# GD32F450_External_Expansion_Camera__V1_0.net
KiCad netlist of a schematic drawn in Altium Designer
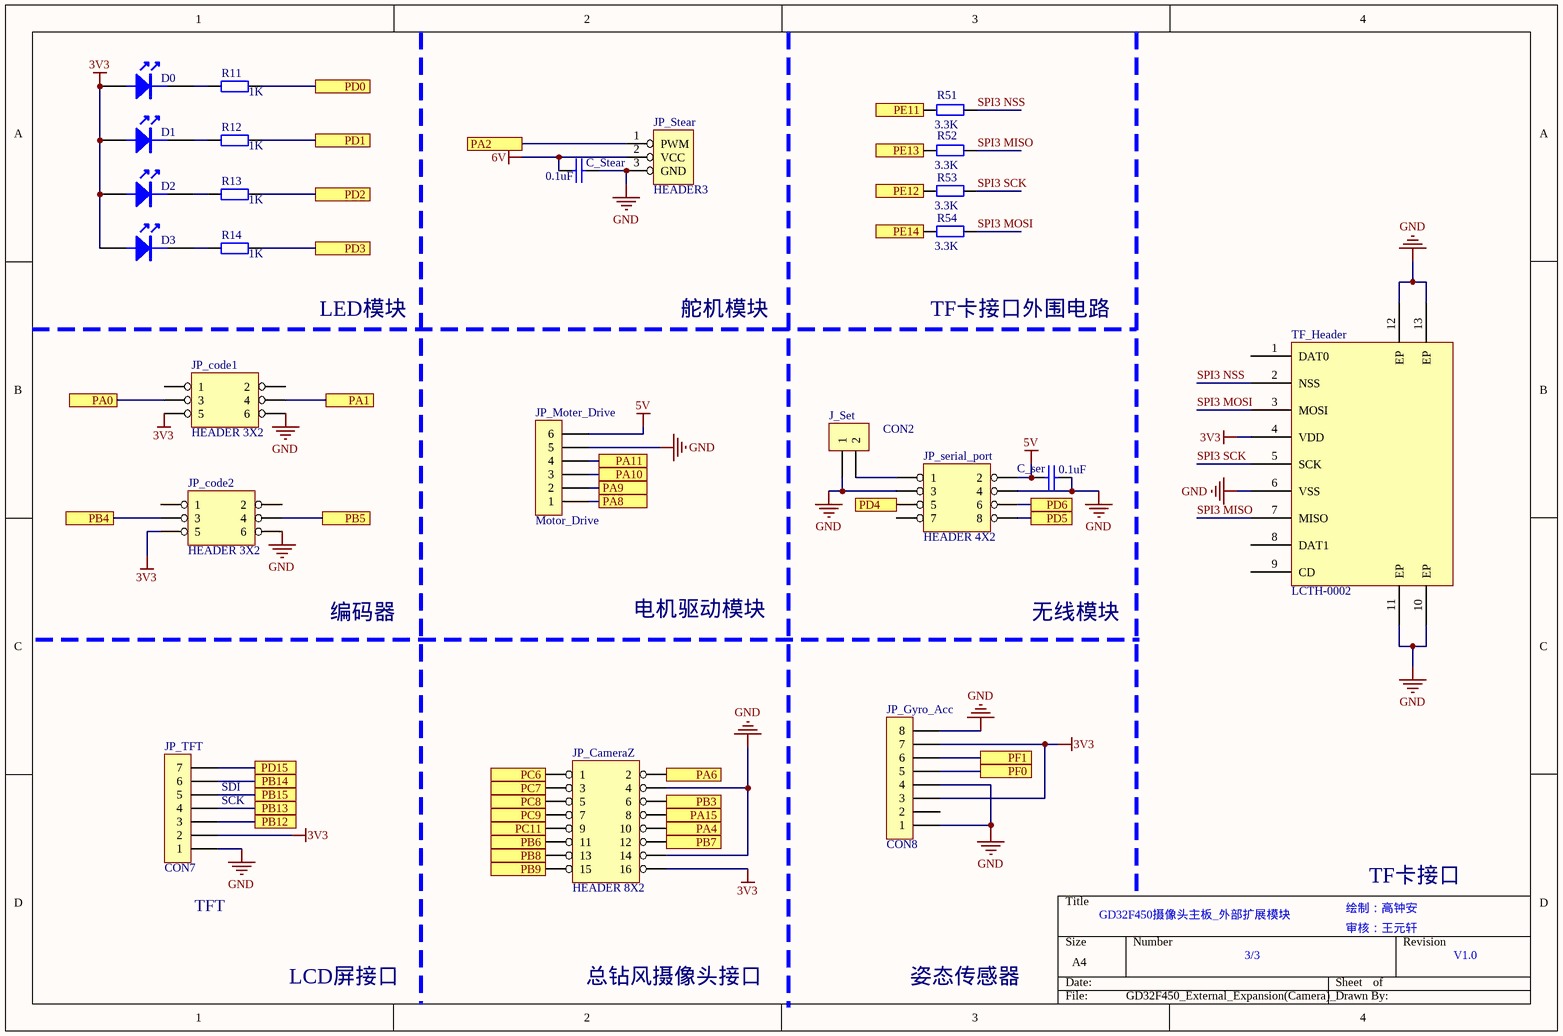
[diagram p0: GD32F450_External_Expansion(Camera)_V1.0.SchDoc]

(export (version "E")
  (design (tool "Eeschema 10.0.6"))
  (components
    (comp (ref "C_ser")
      (value "0.1uF")
      (footprint "0805C")
      (description "Capacitor")
      (libsource (lib "Protel99Lib_SCH") (part "CAP"))
    )
    (comp (ref "C_Stear")
      (value "0.1uF")
      (footprint "0805C")
      (description "Capacitor")
      (libsource (lib "Protel99Lib_SCH") (part "CAP"))
    )
    (comp (ref "D0") (value "LED") (footprint "1206LED") (libsource (lib "Protel99Lib_SCH") (part "LED")))
    (comp (ref "D1") (value "LED") (footprint "1206LED") (libsource (lib "Protel99Lib_SCH") (part "LED")))
    (comp (ref "D2") (value "LED") (footprint "1206LED") (libsource (lib "Protel99Lib_SCH") (part "LED")))
    (comp (ref "D3") (value "LED") (footprint "1206LED") (libsource (lib "Protel99Lib_SCH") (part "LED")))
    (comp (ref "JP_CameraZ")
      (value "HEADER 8X2")
      (footprint "IDC16-JLC")
      (libsource (lib "Protel99Lib_SCH") (part "HEADER 8X2"))
    )
    (comp (ref "JP_code1")
      (value "HEADER 3X2")
      (footprint "IDC6-JLC")
      (libsource (lib "Protel99Lib_SCH") (part "HEADER 3X2"))
    )
    (comp (ref "JP_code2")
      (value "HEADER 3X2")
      (footprint "IDC6-JLC")
      (libsource (lib "Protel99Lib_SCH") (part "HEADER 3X2"))
    )
    (comp (ref "JP_Gyro_Acc")
      (value "CON8")
      (footprint "SIP8")
      (description "Connector")
      (libsource (lib "Protel99Lib_SCH") (part "CON8"))
    )
    (comp (ref "JP_Moter_Drive")
      (value "Motor_Drive")
      (footprint "SIP6N")
      (description "Connector")
      (libsource (lib "Protel99Lib_SCH") (part "CON6"))
    )
    (comp (ref "JP_serial_port")
      (value "HEADER 4X2")
      (footprint "IDC8-JLC")
      (libsource (lib "Protel99Lib_SCH") (part "HEADER 4X2"))
    )
    (comp (ref "JP_Stear") (value "HEADER3") (footprint "SIP3") (libsource (lib "Main_Board") (part "STEER")))
    (comp (ref "JP_TFT")
      (value "CON7")
      (footprint "SIP7")
      (description "Connector")
      (libsource (lib "Protel99Lib_SCH") (part "CON7"))
    )
    (comp (ref "J_Set")
      (value "CON2")
      (footprint "SIP2")
      (description "Connector")
      (libsource (lib "Protel99Lib_SCH") (part "CON2"))
    )
    (comp (ref "R11")
      (value "1K")
      (footprint "0805R")
      (description "Resistor")
      (fields (field (name "Comment") "Res2") (field (name "PUBLISHER") "Altium Limited"))
      (libsource (lib "Miscellaneous Devices") (part "Res2"))
    )
    (comp (ref "R12")
      (value "1K")
      (footprint "0805R")
      (description "Resistor")
      (fields (field (name "Comment") "Res2") (field (name "PUBLISHER") "Altium Limited"))
      (libsource (lib "Miscellaneous Devices") (part "Res2"))
    )
    (comp (ref "R13")
      (value "1K")
      (footprint "0805R")
      (description "Resistor")
      (fields (field (name "Comment") "Res2") (field (name "PUBLISHER") "Altium Limited"))
      (libsource (lib "Miscellaneous Devices") (part "Res2"))
    )
    (comp (ref "R14")
      (value "1K")
      (footprint "0805R")
      (description "Resistor")
      (fields (field (name "Comment") "Res2") (field (name "PUBLISHER") "Altium Limited"))
      (libsource (lib "Miscellaneous Devices") (part "Res2"))
    )
    (comp (ref "R51")
      (value "3.3K")
      (footprint "0805R")
      (description "Resistor")
      (fields (field (name "PUBLISHER") "Altium Limited"))
      (libsource (lib "Miscellaneous Devices") (part "Res2"))
    )
    (comp (ref "R52")
      (value "3.3K")
      (footprint "0805R")
      (description "Resistor")
      (fields (field (name "PUBLISHER") "Altium Limited"))
      (libsource (lib "Miscellaneous Devices") (part "Res2"))
    )
    (comp (ref "R53")
      (value "3.3K")
      (footprint "0805R")
      (description "Resistor")
      (fields (field (name "PUBLISHER") "Altium Limited"))
      (libsource (lib "Miscellaneous Devices") (part "Res2"))
    )
    (comp (ref "R54")
      (value "3.3K")
      (footprint "0805R")
      (description "Resistor")
      (fields (field (name "PUBLISHER") "Altium Limited"))
      (libsource (lib "Miscellaneous Devices") (part "Res2"))
    )
    (comp (ref "TF_Header")
      (value "LCTH-0002")
      (footprint "TF_2")
      (libsource (lib "Schlib1") (part "Component_2"))
    )
  )
  (nets
    (net (code "1") (name "/PA0") (class "Default")
      (node (ref "JP_code1") (pin "3") (pinfunction "3_3") (pintype "passive"))
    )
    (net (code "2") (name "/PA1") (class "Default")
      (node (ref "JP_code1") (pin "4") (pinfunction "4_4") (pintype "passive"))
    )
    (net (code "3") (name "/PA2") (class "Default")
      (node (ref "JP_Stear") (pin "1") (pinfunction "PWM_1") (pintype "passive"))
    )
    (net (code "4") (name "/PA4") (class "Default")
      (node (ref "JP_CameraZ") (pin "10") (pinfunction "10_10") (pintype "passive"))
    )
    (net (code "5") (name "/PA6") (class "Default")
      (node (ref "JP_CameraZ") (pin "2") (pinfunction "2_2") (pintype "passive"))
    )
    (net (code "6") (name "/PA8") (class "Default")
      (node (ref "JP_Moter_Drive") (pin "1") (pinfunction "1_1") (pintype "passive"))
    )
    (net (code "7") (name "/PA9") (class "Default")
      (node (ref "JP_Moter_Drive") (pin "2") (pinfunction "2_2") (pintype "passive"))
    )
    (net (code "8") (name "/PA10") (class "Default")
      (node (ref "JP_Moter_Drive") (pin "3") (pinfunction "3_3") (pintype "passive"))
    )
    (net (code "9") (name "/PA11") (class "Default")
      (node (ref "JP_Moter_Drive") (pin "4") (pinfunction "4_4") (pintype "passive"))
    )
    (net (code "10") (name "/PA15") (class "Default")
      (node (ref "JP_CameraZ") (pin "8") (pinfunction "8_8") (pintype "passive"))
    )
    (net (code "11") (name "/PB3") (class "Default")
      (node (ref "JP_CameraZ") (pin "6") (pinfunction "6_6") (pintype "passive"))
    )
    (net (code "12") (name "/PB4") (class "Default")
      (node (ref "JP_code2") (pin "3") (pinfunction "3_3") (pintype "passive"))
    )
    (net (code "13") (name "/PB5") (class "Default")
      (node (ref "JP_code2") (pin "4") (pinfunction "4_4") (pintype "passive"))
    )
    (net (code "14") (name "/PB6") (class "Default")
      (node (ref "JP_CameraZ") (pin "11") (pinfunction "11_11") (pintype "passive"))
    )
    (net (code "15") (name "/PB7") (class "Default")
      (node (ref "JP_CameraZ") (pin "12") (pinfunction "12_12") (pintype "passive"))
    )
    (net (code "16") (name "/PB8") (class "Default")
      (node (ref "JP_CameraZ") (pin "13") (pinfunction "13_13") (pintype "passive"))
    )
    (net (code "17") (name "/PB9") (class "Default")
      (node (ref "JP_CameraZ") (pin "15") (pinfunction "15_15") (pintype "passive"))
    )
    (net (code "18") (name "/PB12") (class "Default")
      (node (ref "JP_TFT") (pin "3") (pinfunction "3_3") (pintype "passive"))
    )
    (net (code "19") (name "/PB13") (class "Default")
      (node (ref "JP_TFT") (pin "4") (pinfunction "4_4") (pintype "passive"))
    )
    (net (code "20") (name "/PB14") (class "Default")
      (node (ref "JP_TFT") (pin "6") (pinfunction "6_6") (pintype "passive"))
    )
    (net (code "21") (name "/PB15") (class "Default")
      (node (ref "JP_TFT") (pin "5") (pinfunction "5_5") (pintype "passive"))
    )
    (net (code "22") (name "/PC6") (class "Default")
      (node (ref "JP_CameraZ") (pin "1") (pinfunction "1_1") (pintype "passive"))
    )
    (net (code "23") (name "/PC7") (class "Default")
      (node (ref "JP_CameraZ") (pin "3") (pinfunction "3_3") (pintype "passive"))
    )
    (net (code "24") (name "/PC8") (class "Default")
      (node (ref "JP_CameraZ") (pin "5") (pinfunction "5_5") (pintype "passive"))
    )
    (net (code "25") (name "/PC9") (class "Default")
      (node (ref "JP_CameraZ") (pin "7") (pinfunction "7_7") (pintype "passive"))
    )
    (net (code "26") (name "/PC11") (class "Default")
      (node (ref "JP_CameraZ") (pin "9") (pinfunction "9_9") (pintype "passive"))
    )
    (net (code "27") (name "/PD0") (class "Default")
      (node (ref "R11") (pin "2") (pinfunction "2_2") (pintype "passive"))
    )
    (net (code "28") (name "/PD1") (class "Default")
      (node (ref "R12") (pin "2") (pinfunction "2_2") (pintype "passive"))
    )
    (net (code "29") (name "/PD2") (class "Default")
      (node (ref "R13") (pin "2") (pinfunction "2_2") (pintype "passive"))
    )
    (net (code "30") (name "/PD3") (class "Default")
      (node (ref "R14") (pin "2") (pinfunction "2_2") (pintype "passive"))
    )
    (net (code "31") (name "/PD4") (class "Default")
      (node (ref "JP_serial_port") (pin "5") (pinfunction "5_5") (pintype "passive"))
    )
    (net (code "32") (name "/PD5") (class "Default")
      (node (ref "JP_serial_port") (pin "8") (pinfunction "8_8") (pintype "passive"))
    )
    (net (code "33") (name "/PD6") (class "Default")
      (node (ref "JP_serial_port") (pin "6") (pinfunction "6_6") (pintype "passive"))
    )
    (net (code "34") (name "/PD15") (class "Default")
      (node (ref "JP_TFT") (pin "7") (pinfunction "7_7") (pintype "passive"))
    )
    (net (code "35") (name "/PE11") (class "Default")
      (node (ref "R51") (pin "1") (pinfunction "1_1") (pintype "passive"))
    )
    (net (code "36") (name "/PE12") (class "Default")
      (node (ref "R53") (pin "1") (pinfunction "1_1") (pintype "passive"))
    )
    (net (code "37") (name "/PE13") (class "Default")
      (node (ref "R52") (pin "1") (pinfunction "1_1") (pintype "passive"))
    )
    (net (code "38") (name "/PE14") (class "Default")
      (node (ref "R54") (pin "1") (pinfunction "1_1") (pintype "passive"))
    )
    (net (code "39") (name "/PF0") (class "Default")
      (node (ref "JP_Gyro_Acc") (pin "5") (pinfunction "5_5") (pintype "passive"))
    )
    (net (code "40") (name "/PF1") (class "Default")
      (node (ref "JP_Gyro_Acc") (pin "6") (pinfunction "6_6") (pintype "passive"))
    )
    (net (code "41") (name "/SPI3 MISO") (class "Default")
      (node (ref "R52") (pin "2") (pinfunction "2_2") (pintype "passive"))
      (node (ref "TF_Header") (pin "7") (pinfunction "MISO_7") (pintype "passive"))
    )
    (net (code "42") (name "/SPI3 MOSI") (class "Default")
      (node (ref "R54") (pin "2") (pinfunction "2_2") (pintype "passive"))
      (node (ref "TF_Header") (pin "3") (pinfunction "MOSI_3") (pintype "passive"))
    )
    (net (code "43") (name "/SPI3 NSS") (class "Default")
      (node (ref "R51") (pin "2") (pinfunction "2_2") (pintype "passive"))
      (node (ref "TF_Header") (pin "2") (pinfunction "NSS_2") (pintype "passive"))
    )
    (net (code "44") (name "/SPI3 SCK") (class "Default")
      (node (ref "R53") (pin "2") (pinfunction "2_2") (pintype "passive"))
      (node (ref "TF_Header") (pin "5") (pinfunction "SCK_5") (pintype "passive"))
    )
    (net (code "45") (name "3V3") (class "Default")
      (node (ref "D0") (pin "A") (pinfunction "1_A") (pintype "passive"))
      (node (ref "D1") (pin "A") (pinfunction "1_A") (pintype "passive"))
      (node (ref "D2") (pin "A") (pinfunction "1_A") (pintype "passive"))
      (node (ref "D3") (pin "A") (pinfunction "1_A") (pintype "passive"))
      (node (ref "JP_CameraZ") (pin "16") (pinfunction "16_16") (pintype "passive"))
      (node (ref "JP_Gyro_Acc") (pin "3") (pinfunction "3_3") (pintype "passive"))
      (node (ref "JP_Gyro_Acc") (pin "7") (pinfunction "7_7") (pintype "passive"))
      (node (ref "JP_TFT") (pin "2") (pinfunction "2_2") (pintype "passive"))
      (node (ref "JP_code1") (pin "5") (pinfunction "5_5") (pintype "passive"))
      (node (ref "JP_code2") (pin "5") (pinfunction "5_5") (pintype "passive"))
      (node (ref "TF_Header") (pin "4") (pinfunction "VDD_4") (pintype "passive"))
    )
    (net (code "46") (name "5V") (class "Default")
      (node (ref "C_ser") (pin "1") (pinfunction "1_1") (pintype "passive"))
      (node (ref "JP_Moter_Drive") (pin "6") (pinfunction "6_6") (pintype "passive"))
      (node (ref "JP_serial_port") (pin "2") (pinfunction "2_2") (pintype "passive"))
    )
    (net (code "47") (name "6V") (class "Default")
      (node (ref "C_Stear") (pin "1") (pinfunction "1_1") (pintype "passive"))
      (node (ref "JP_Stear") (pin "2") (pinfunction "VCC_2") (pintype "passive"))
    )
    (net (code "48") (name "GND") (class "Default")
      (node (ref "C_Stear") (pin "2") (pinfunction "2_2") (pintype "passive"))
      (node (ref "C_ser") (pin "2") (pinfunction "2_2") (pintype "passive"))
      (node (ref "JP_CameraZ") (pin "14") (pinfunction "14_14") (pintype "passive"))
      (node (ref "JP_CameraZ") (pin "4") (pinfunction "4_4") (pintype "passive"))
      (node (ref "JP_Gyro_Acc") (pin "1") (pinfunction "1_1") (pintype "passive"))
      (node (ref "JP_Gyro_Acc") (pin "4") (pinfunction "4_4") (pintype "passive"))
      (node (ref "JP_Gyro_Acc") (pin "8") (pinfunction "8_8") (pintype "passive"))
      (node (ref "JP_Moter_Drive") (pin "5") (pinfunction "5_5") (pintype "passive"))
      (node (ref "JP_Stear") (pin "3") (pinfunction "GND_3") (pintype "passive"))
      (node (ref "JP_TFT") (pin "1") (pinfunction "1_1") (pintype "passive"))
      (node (ref "JP_code1") (pin "6") (pinfunction "6_6") (pintype "passive"))
      (node (ref "JP_code2") (pin "6") (pinfunction "6_6") (pintype "passive"))
      (node (ref "JP_serial_port") (pin "3") (pinfunction "3_3") (pintype "passive"))
      (node (ref "JP_serial_port") (pin "4") (pinfunction "4_4") (pintype "passive"))
      (node (ref "J_Set") (pin "1") (pinfunction "1_1") (pintype "passive"))
      (node (ref "TF_Header") (pin "10") (pinfunction "EP_10") (pintype "passive"))
      (node (ref "TF_Header") (pin "11") (pinfunction "EP_11") (pintype "passive"))
      (node (ref "TF_Header") (pin "12") (pinfunction "EP_12") (pintype "passive"))
      (node (ref "TF_Header") (pin "13") (pinfunction "EP_13") (pintype "passive"))
      (node (ref "TF_Header") (pin "6") (pinfunction "VSS_6") (pintype "passive"))
    )
    (net (code "49") (name "Net-(D0-2)") (class "Default")
      (node (ref "D0") (pin "K") (pinfunction "2_K") (pintype "passive"))
      (node (ref "R11") (pin "1") (pinfunction "1_1") (pintype "passive"))
    )
    (net (code "50") (name "Net-(D1-2)") (class "Default")
      (node (ref "D1") (pin "K") (pinfunction "2_K") (pintype "passive"))
      (node (ref "R12") (pin "1") (pinfunction "1_1") (pintype "passive"))
    )
    (net (code "51") (name "Net-(D2-2)") (class "Default")
      (node (ref "D2") (pin "K") (pinfunction "2_K") (pintype "passive"))
      (node (ref "R13") (pin "1") (pinfunction "1_1") (pintype "passive"))
    )
    (net (code "52") (name "Net-(D3-2)") (class "Default")
      (node (ref "D3") (pin "K") (pinfunction "2_K") (pintype "passive"))
      (node (ref "R14") (pin "1") (pinfunction "1_1") (pintype "passive"))
    )
    (net (code "53") (name "Net-(JP_serial_port-Pad1)") (class "Default")
      (node (ref "JP_serial_port") (pin "1") (pinfunction "1_1") (pintype "passive"))
      (node (ref "J_Set") (pin "2") (pinfunction "2_2") (pintype "passive"))
    )
    (net (code "54") (name "unconnected-(JP_Gyro_Acc-Pad2)") (class "Default")
      (node (ref "JP_Gyro_Acc") (pin "2") (pinfunction "2_2") (pintype "passive"))
    )
    (net (code "55") (name "unconnected-(JP_code1-Pad1)") (class "Default")
      (node (ref "JP_code1") (pin "1") (pinfunction "1_1") (pintype "passive"))
    )
    (net (code "56") (name "unconnected-(JP_code1-Pad2)") (class "Default")
      (node (ref "JP_code1") (pin "2") (pinfunction "2_2") (pintype "passive"))
    )
    (net (code "57") (name "unconnected-(JP_code2-Pad1)") (class "Default")
      (node (ref "JP_code2") (pin "1") (pinfunction "1_1") (pintype "passive"))
    )
    (net (code "58") (name "unconnected-(JP_code2-Pad2)") (class "Default")
      (node (ref "JP_code2") (pin "2") (pinfunction "2_2") (pintype "passive"))
    )
    (net (code "59") (name "unconnected-(JP_serial_port-Pad7)") (class "Default")
      (node (ref "JP_serial_port") (pin "7") (pinfunction "7_7") (pintype "passive"))
    )
    (net (code "60") (name "unconnected-(TF_Header-CD-Pad9)") (class "Default")
      (node (ref "TF_Header") (pin "9") (pinfunction "CD_9") (pintype "passive"))
    )
    (net (code "61") (name "unconnected-(TF_Header-DAT0-Pad1)") (class "Default")
      (node (ref "TF_Header") (pin "1") (pinfunction "DAT0_1") (pintype "passive"))
    )
    (net (code "62") (name "unconnected-(TF_Header-DAT1-Pad8)") (class "Default")
      (node (ref "TF_Header") (pin "8") (pinfunction "DAT1_8") (pintype "passive"))
    )
  )
)
